# 11.net
KiCad netlist of a schematic drawn in Altium Designer
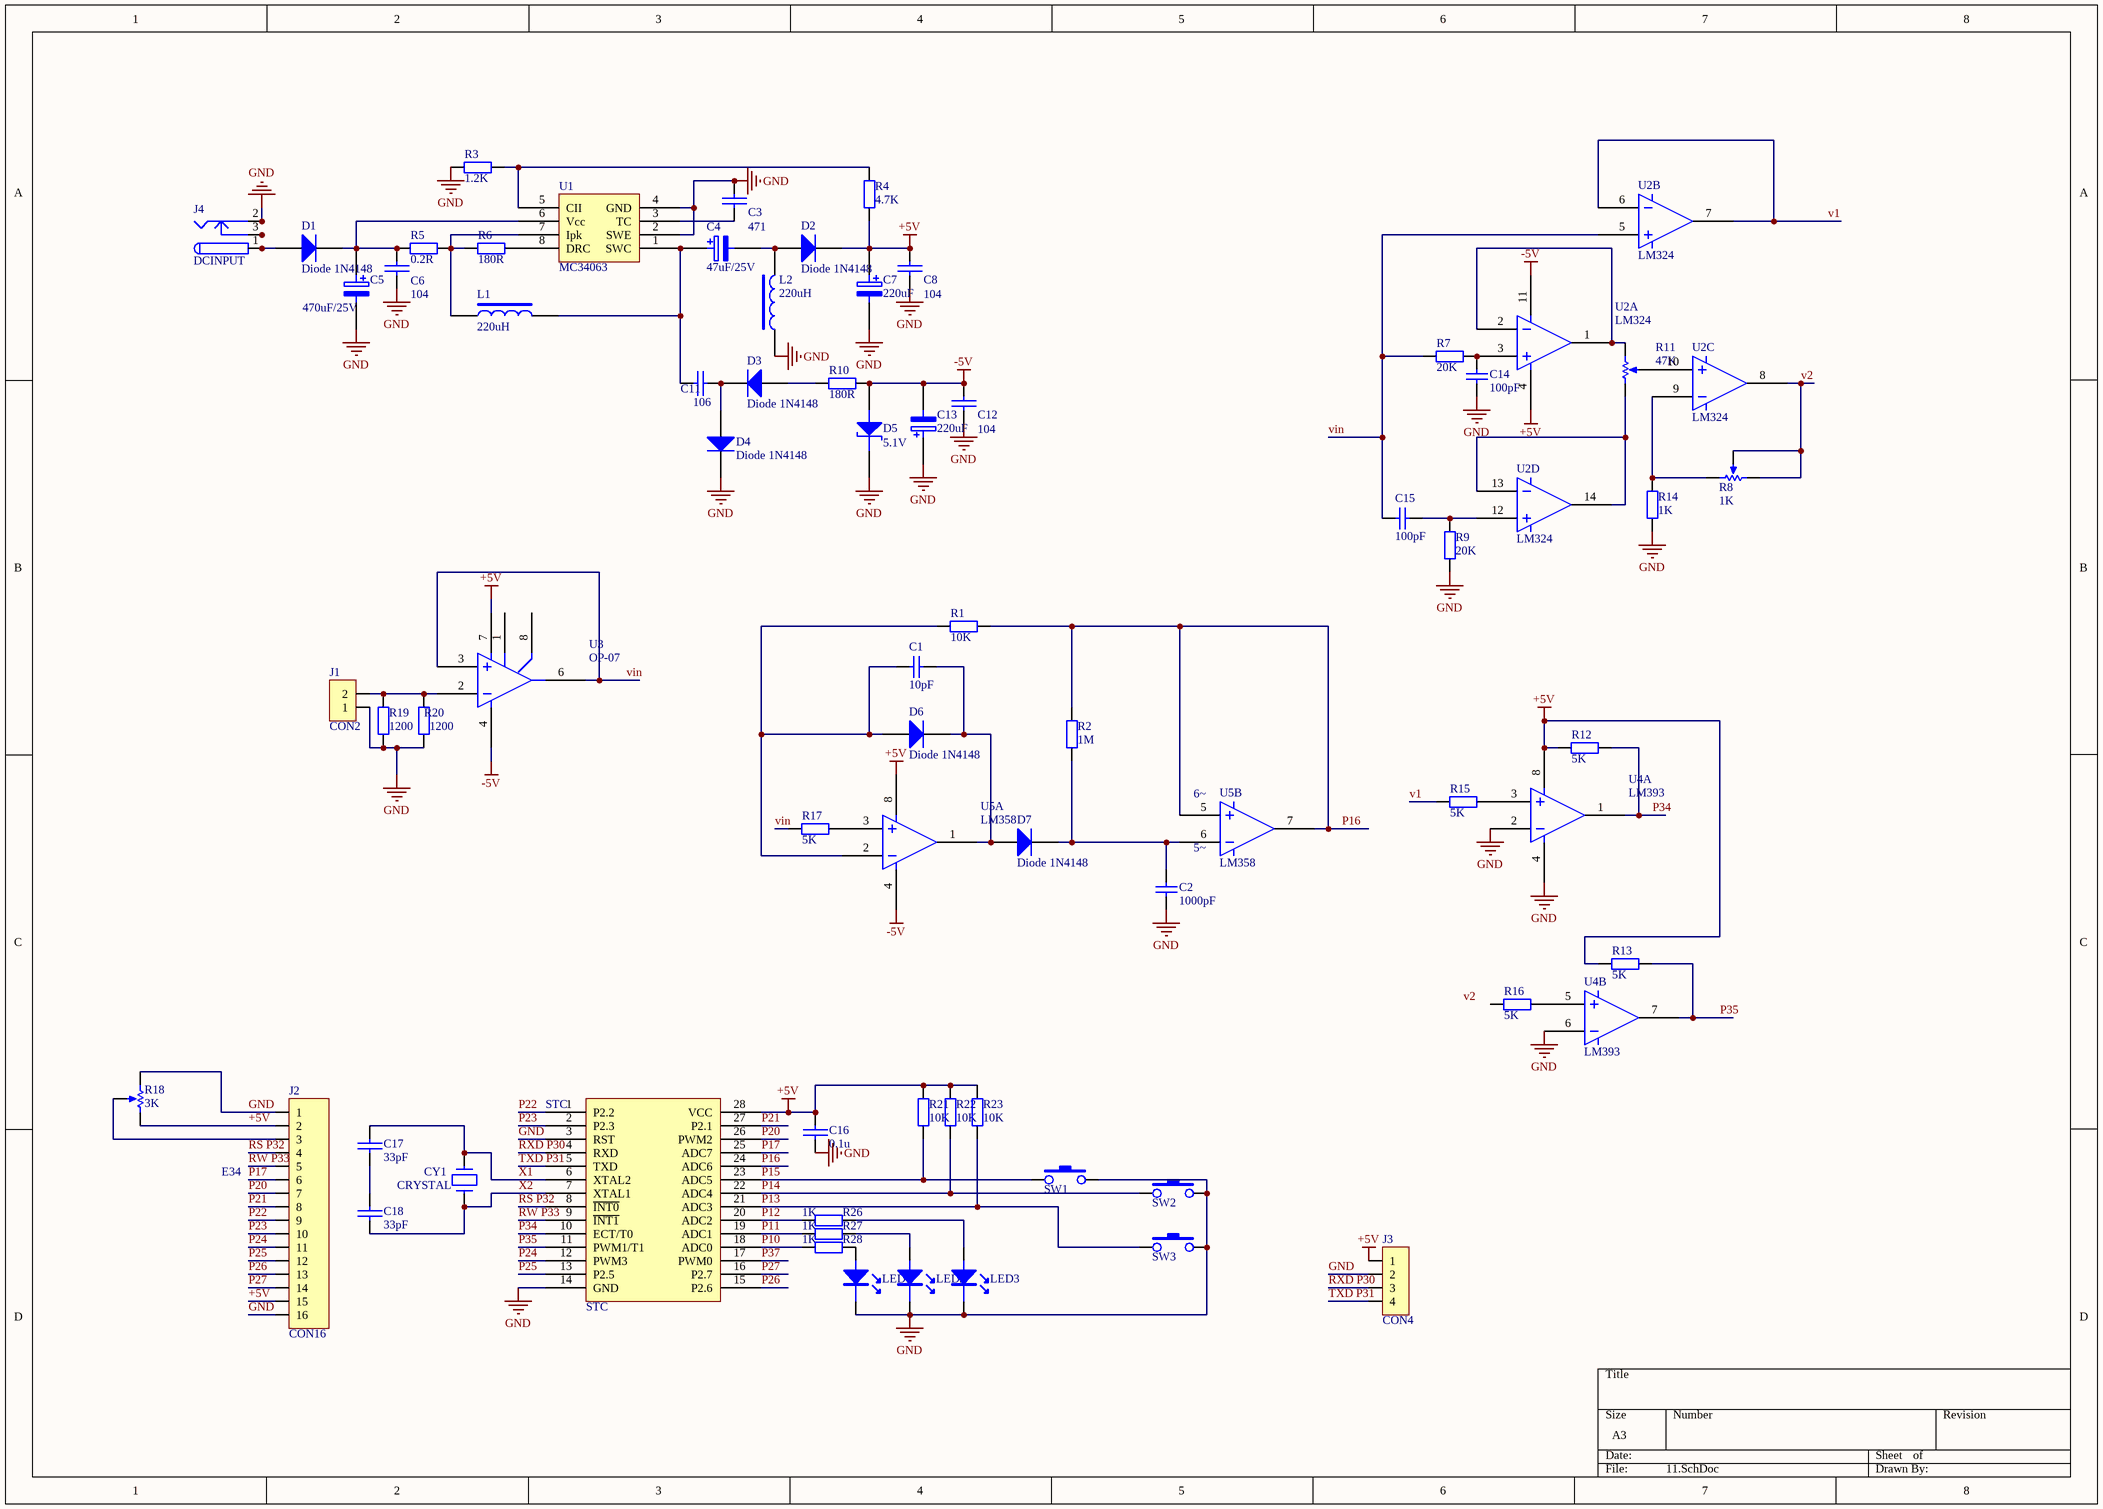
[diagram p0: 11.SchDoc]

(export (version "E")
  (design (tool "Eeschema 10.0.6"))
  (components
    (comp (ref "C1")
      (value "10pF")
      (footprint "RAD-0.2")
      (description "Capacitor")
      (fields (field (name "Comment") "Cap") (field (name "PUBLISHER") "Altium Limited"))
      (libsource (lib "Miscellaneous Devices") (part "Cap"))
    )
    (comp (ref "C2")
      (value "1000pF")
      (footprint "RAD-0.2")
      (description "Capacitor")
      (fields (field (name "Comment") "Cap") (field (name "PUBLISHER") "Altium Limited"))
      (libsource (lib "Miscellaneous Devices") (part "Cap"))
    )
    (comp (ref "C3")
      (value "471")
      (footprint "RAD0.2")
      (description "Capacitor")
      (libsource (lib "Miscellaneous Devices") (part "CAP"))
    )
    (comp (ref "C4")
      (value "47uF/25V")
      (footprint "RB.2/.3")
      (description "Electrolytic Capacitor")
      (libsource (lib "Miscellaneous Devices") (part "ELECTRO2"))
    )
    (comp (ref "C5")
      (value "470uF/25V")
      (footprint "RB.2/.3")
      (description "Electrolytic Capacitor")
      (libsource (lib "Miscellaneous Devices") (part "ELECTRO2"))
    )
    (comp (ref "C6")
      (value "104")
      (footprint "RAD0.2")
      (description "Capacitor")
      (libsource (lib "Miscellaneous Devices") (part "CAP"))
    )
    (comp (ref "C7")
      (value "220uF")
      (footprint "RB.2/.3")
      (description "Electrolytic Capacitor")
      (libsource (lib "Miscellaneous Devices") (part "ELECTRO2"))
    )
    (comp (ref "C8")
      (value "104")
      (footprint "RAD0.2")
      (description "Capacitor")
      (libsource (lib "Miscellaneous Devices") (part "CAP"))
    )
    (comp (ref "C11")
      (value "106")
      (footprint "RAD0.2")
      (description "Capacitor")
      (libsource (lib "Miscellaneous Devices") (part "CAP"))
    )
    (comp (ref "C12")
      (value "104")
      (footprint "RAD0.2")
      (description "Capacitor")
      (libsource (lib "Miscellaneous Devices") (part "CAP"))
    )
    (comp (ref "C13")
      (value "220uF")
      (footprint "RB.2/.3")
      (description "Electrolytic Capacitor")
      (libsource (lib "Miscellaneous Devices") (part "ELECTRO2"))
    )
    (comp (ref "C14")
      (value "100pF")
      (footprint "RAD-0.2")
      (description "Capacitor")
      (fields (field (name "Comment") "Cap") (field (name "PUBLISHER") "Altium Limited"))
      (libsource (lib "Miscellaneous Devices") (part "Cap"))
    )
    (comp (ref "C15")
      (value "100pF")
      (footprint "RAD-0.2")
      (description "Capacitor")
      (fields (field (name "Comment") "Cap") (field (name "PUBLISHER") "Altium Limited"))
      (libsource (lib "Miscellaneous Devices") (part "Cap"))
    )
    (comp (ref "C16") (value "0.1u") (footprint "RAD0.2") (libsource (lib "_JINXD-DEVICE") (part "CAP")))
    (comp (ref "C17") (value "33pF") (footprint "RAD0.2") (libsource (lib "_JINXD-DEVICE") (part "CAP")))
    (comp (ref "C18") (value "33pF") (footprint "RAD0.2") (libsource (lib "_JINXD-DEVICE") (part "CAP")))
    (comp (ref "CY1") (value "CRYSTAL") (footprint "CY2") (libsource (lib "_JINXD-DEVICE") (part "CRYSTAL")))
    (comp (ref "D1")
      (value "Diode 1N4148")
      (footprint "DIODE-0.4")
      (description "High Conductance Fast Diode")
      (fields (field (name "PUBLISHER") "Altium Limited"))
      (libsource (lib "Miscellaneous Devices") (part "Diode 1N4148"))
    )
    (comp (ref "D2")
      (value "Diode 1N4148")
      (footprint "DIODE-0.4")
      (description "High Conductance Fast Diode")
      (fields (field (name "PUBLISHER") "Altium Limited"))
      (libsource (lib "Miscellaneous Devices") (part "Diode 1N4148"))
    )
    (comp (ref "D3")
      (value "Diode 1N4148")
      (footprint "DIODE-0.4")
      (description "High Conductance Fast Diode")
      (fields (field (name "PUBLISHER") "Altium Limited"))
      (libsource (lib "Miscellaneous Devices") (part "Diode 1N4148"))
    )
    (comp (ref "D4")
      (value "Diode 1N4148")
      (footprint "DIODE-0.4")
      (description "High Conductance Fast Diode")
      (fields (field (name "PUBLISHER") "Altium Limited"))
      (libsource (lib "Miscellaneous Devices") (part "Diode 1N4148"))
    )
    (comp (ref "D5")
      (value "5.1V")
      (footprint "AXIAL0.4")
      (description "Zener Diode")
      (libsource (lib "Miscellaneous Devices") (part "ZENER2"))
    )
    (comp (ref "D6")
      (value "Diode 1N4148")
      (footprint "DIODE-0.4")
      (description "High Conductance Fast Diode")
      (fields (field (name "PUBLISHER") "Altium Limited"))
      (libsource (lib "Miscellaneous Devices") (part "Diode 1N4148"))
    )
    (comp (ref "D7")
      (value "Diode 1N4148")
      (footprint "DIODE-0.4")
      (description "High Conductance Fast Diode")
      (fields (field (name "PUBLISHER") "Altium Limited"))
      (libsource (lib "Miscellaneous Devices") (part "Diode 1N4148"))
    )
    (comp (ref "J1") (value "CON2") (footprint "SIP2") (libsource (lib "_JINXD-DEVICE") (part "CON2")))
    (comp (ref "J2") (value "CON16") (footprint "SIP16") (libsource (lib "_JINXD-DEVICE") (part "CON16")))
    (comp (ref "J3") (value "CON4") (footprint "SIP4") (libsource (lib "_JINXD-DEVICE") (part "CON4")))
    (comp (ref "J4")
      (value "DCINPUT")
      (footprint "DC-INPUT")
      (description "Low Voltage Power Supply Connector")
      (fields (field (name "PUBLISHER") "Altium Limited"))
      (libsource (lib "Miscellaneous Connectors") (part "PWR2.5"))
    )
    (comp (ref "L1")
      (value "220uH")
      (footprint "_Jinxd-PCB:RB.2/.4")
      (libsource (lib "Miscellaneous Devices") (part "INDUCTOR2"))
    )
    (comp (ref "L2")
      (value "220uH")
      (footprint "_Jinxd-PCB:RB.2/.4")
      (libsource (lib "") (part "INDUCTOR2_1"))
    )
    (comp (ref "LED1") (value "LED") (footprint "LED") (libsource (lib "_JINXD-DEVICE") (part "LED")))
    (comp (ref "LED2") (value "LED") (footprint "LED") (libsource (lib "_JINXD-DEVICE") (part "LED")))
    (comp (ref "LED3") (value "LED") (footprint "LED") (libsource (lib "_JINXD-DEVICE") (part "LED")))
    (comp (ref "R1")
      (value "10K")
      (footprint "AXIAL-0.4")
      (description "Resistor")
      (fields (field (name "Comment") "Res2") (field (name "PUBLISHER") "Altium Limited"))
      (libsource (lib "") (part "Res2_2"))
    )
    (comp (ref "R2")
      (value "1M")
      (footprint "AXIAL-0.4")
      (description "Resistor")
      (fields (field (name "Comment") "Res2") (field (name "PUBLISHER") "Altium Limited"))
      (libsource (lib "Miscellaneous Devices") (part "Res2"))
    )
    (comp (ref "R3")
      (value "1.2K")
      (footprint "AXIAL-0.4")
      (description "Resistor")
      (fields (field (name "PUBLISHER") "Altium Limited"))
      (libsource (lib "") (part "Res2_2"))
    )
    (comp (ref "R4")
      (value "4.7K")
      (footprint "AXIAL-0.4")
      (description "Resistor")
      (fields (field (name "PUBLISHER") "Altium Limited"))
      (libsource (lib "Miscellaneous Devices") (part "Res2"))
    )
    (comp (ref "R5")
      (value "0.2R")
      (footprint "AXIAL-0.4")
      (description "Resistor")
      (fields (field (name "PUBLISHER") "Altium Limited"))
      (libsource (lib "") (part "Res2_2"))
    )
    (comp (ref "R6")
      (value "180R")
      (footprint "AXIAL-0.4")
      (description "Resistor")
      (fields (field (name "PUBLISHER") "Altium Limited"))
      (libsource (lib "") (part "Res2_2"))
    )
    (comp (ref "R7")
      (value "20K")
      (footprint "AXIAL-0.4")
      (description "Resistor")
      (fields (field (name "PUBLISHER") "Altium Limited"))
      (libsource (lib "") (part "Res2_1"))
    )
    (comp (ref "R8")
      (value "1K")
      (footprint "VR5")
      (description "Potentiometer")
      (fields (field (name "Comment") "RPot") (field (name "PUBLISHER") "Altium Limited"))
      (libsource (lib "Miscellaneous Devices") (part "RPot"))
    )
    (comp (ref "R9")
      (value "20K")
      (footprint "AXIAL-0.4")
      (description "Resistor")
      (fields (field (name "PUBLISHER") "Altium Limited"))
      (libsource (lib "Miscellaneous Devices") (part "Res2"))
    )
    (comp (ref "R10")
      (value "180R")
      (footprint "AXIAL-0.4")
      (description "Resistor")
      (fields (field (name "PUBLISHER") "Altium Limited"))
      (libsource (lib "") (part "Res2_1"))
    )
    (comp (ref "R11")
      (value "47K")
      (footprint "VR5")
      (description "Potentiometer")
      (fields (field (name "PUBLISHER") "Altium Limited"))
      (libsource (lib "Miscellaneous Devices") (part "RPot"))
    )
    (comp (ref "R12")
      (value "5K")
      (footprint "AXIAL-0.4")
      (description "Resistor")
      (fields (field (name "Comment") "Res2") (field (name "PUBLISHER") "Altium Limited"))
      (libsource (lib "") (part "Res2_2"))
    )
    (comp (ref "R13")
      (value "5K")
      (footprint "AXIAL-0.4")
      (description "Resistor")
      (fields (field (name "Comment") "Res2") (field (name "PUBLISHER") "Altium Limited"))
      (libsource (lib "") (part "Res2_2"))
    )
    (comp (ref "R14")
      (value "1K")
      (footprint "AXIAL-0.4")
      (description "Resistor")
      (fields (field (name "Comment") "Res2") (field (name "PUBLISHER") "Altium Limited"))
      (libsource (lib "Miscellaneous Devices") (part "Res2"))
    )
    (comp (ref "R15")
      (value "5K")
      (footprint "AXIAL-0.4")
      (description "Resistor")
      (fields (field (name "PUBLISHER") "Altium Limited"))
      (libsource (lib "") (part "Res2_1"))
    )
    (comp (ref "R16")
      (value "5K")
      (footprint "AXIAL-0.4")
      (description "Resistor")
      (fields (field (name "PUBLISHER") "Altium Limited"))
      (libsource (lib "") (part "Res2_1"))
    )
    (comp (ref "R17")
      (value "5K")
      (footprint "AXIAL-0.4")
      (description "Resistor")
      (fields (field (name "Comment") "Res2") (field (name "PUBLISHER") "Altium Limited"))
      (libsource (lib "") (part "Res2_1"))
    )
    (comp (ref "R18")
      (value "3K")
      (footprint "VR5")
      (description "Potentiometer")
      (fields (field (name "Comment") "RPot") (field (name "PUBLISHER") "Altium Limited"))
      (libsource (lib "Miscellaneous Devices") (part "RPot"))
    )
    (comp (ref "R19")
      (value "1200")
      (footprint "AXIAL-0.4")
      (description "Resistor")
      (fields (field (name "Comment") "Res2") (field (name "PUBLISHER") "Altium Limited"))
      (libsource (lib "Miscellaneous Devices") (part "Res2"))
    )
    (comp (ref "R20")
      (value "1200")
      (footprint "AXIAL-0.4")
      (description "Resistor")
      (fields (field (name "Comment") "Res2") (field (name "PUBLISHER") "Altium Limited"))
      (libsource (lib "Miscellaneous Devices") (part "Res2"))
    )
    (comp (ref "R21")
      (value "10K")
      (footprint "AXIAL-0.4")
      (description "Resistor")
      (fields (field (name "Comment") "Res2") (field (name "PUBLISHER") "Altium Limited"))
      (libsource (lib "Miscellaneous Devices") (part "Res2"))
    )
    (comp (ref "R22")
      (value "10K")
      (footprint "AXIAL-0.4")
      (description "Resistor")
      (fields (field (name "Comment") "Res2") (field (name "PUBLISHER") "Altium Limited"))
      (libsource (lib "Miscellaneous Devices") (part "Res2"))
    )
    (comp (ref "R23")
      (value "10K")
      (footprint "AXIAL-0.4")
      (description "Resistor")
      (fields (field (name "Comment") "Res2") (field (name "PUBLISHER") "Altium Limited"))
      (libsource (lib "Miscellaneous Devices") (part "Res2"))
    )
    (comp (ref "R26")
      (value "1K")
      (footprint "AXIAL-0.4")
      (description "Resistor")
      (fields (field (name "Comment") "Res2") (field (name "PUBLISHER") "Altium Limited"))
      (libsource (lib "") (part "Res2_1"))
    )
    (comp (ref "R27")
      (value "1K")
      (footprint "AXIAL-0.4")
      (description "Resistor")
      (fields (field (name "Comment") "Res2") (field (name "PUBLISHER") "Altium Limited"))
      (libsource (lib "") (part "Res2_1"))
    )
    (comp (ref "R28")
      (value "1K")
      (footprint "AXIAL-0.4")
      (description "Resistor")
      (fields (field (name "Comment") "Res2") (field (name "PUBLISHER") "Altium Limited"))
      (libsource (lib "") (part "Res2_1"))
    )
    (comp (ref "STC") (value "STC") (footprint "DIP28") (libsource (lib "STC12C5628AD") (part "Component_1")))
    (comp (ref "SW1") (value "SW-PB") (footprint "SW-BP") (libsource (lib "_JINXD-DEVICE") (part "SW-PB")))
    (comp (ref "SW2") (value "SW-PB") (footprint "SW-BP") (libsource (lib "_JINXD-DEVICE") (part "SW-PB")))
    (comp (ref "SW3") (value "SW-PB") (footprint "SW-BP") (libsource (lib "_JINXD-DEVICE") (part "SW-PB")))
    (comp (ref "U1") (value "MC34063") (footprint "DIP8") (libsource (lib "_JINXD-DEVICE") (part "MC34063")))
    (comp (ref "U2")
      (value "LM324")
      (footprint "DIP-14")
      (libsource (lib "Schematic Operational Amplifiers") (part "LM324"))
    )
    (comp (ref "U3")
      (value "OP-07")
      (footprint "DIP-8")
      (libsource (lib "Schematic Operational Amplifiers") (part "OP-07"))
    )
    (comp (ref "U4")
      (value "LM393")
      (footprint "DIP-8")
      (libsource (lib "Schematic Comparator") (part "LM393"))
    )
    (comp (ref "U5")
      (value "LM358")
      (footprint "DIP-8")
      (libsource (lib "Schematic Operational Amplifiers") (part "LM358"))
    )
  )
  (nets
    (net (code "1") (name "+5V") (class "Default")
      (node (ref "C16") (pin "1") (pintype "passive"))
      (node (ref "C7") (pin "1") (pinfunction "1_1") (pintype "passive"))
      (node (ref "C8") (pin "1") (pinfunction "1_1") (pintype "passive"))
      (node (ref "D2") (pin "2") (pinfunction "K_2") (pintype "passive"))
      (node (ref "J2") (pin "15") (pinfunction "15_15") (pintype "passive"))
      (node (ref "J2") (pin "2") (pinfunction "2_2") (pintype "passive"))
      (node (ref "J3") (pin "1") (pinfunction "1_1") (pintype "passive"))
      (node (ref "R12") (pin "1") (pinfunction "1_1") (pintype "passive"))
      (node (ref "R13") (pin "1") (pinfunction "1_1") (pintype "passive"))
      (node (ref "R18") (pin "2") (pinfunction "BOT_2") (pintype "passive"))
      (node (ref "R21") (pin "2") (pinfunction "2_2") (pintype "passive"))
      (node (ref "R22") (pin "2") (pinfunction "2_2") (pintype "passive"))
      (node (ref "R23") (pin "2") (pinfunction "2_2") (pintype "passive"))
      (node (ref "R4") (pin "1") (pinfunction "1_1") (pintype "passive"))
      (node (ref "STC") (pin "28") (pinfunction "VCC_28") (pintype "passive"))
      (node (ref "U2") (pin "4") (pintype "passive"))
      (node (ref "U3") (pin "7") (pintype "passive"))
      (node (ref "U4") (pin "8") (pintype "passive"))
      (node (ref "U5") (pin "8") (pintype "passive"))
    )
    (net (code "2") (name "-5V") (class "Default")
      (node (ref "C12") (pin "1") (pinfunction "1_1") (pintype "passive"))
      (node (ref "C13") (pin "2") (pinfunction "2_2") (pintype "passive"))
      (node (ref "D5") (pin "1") (pinfunction "A_1") (pintype "passive"))
      (node (ref "R10") (pin "1") (pinfunction "1_1") (pintype "passive"))
      (node (ref "U2") (pin "11") (pintype "passive"))
      (node (ref "U3") (pin "4") (pintype "passive"))
      (node (ref "U5") (pin "4") (pintype "passive"))
    )
    (net (code "3") (name "/P10") (class "Default")
      (node (ref "R28") (pin "2") (pinfunction "2_2") (pintype "passive"))
      (node (ref "STC") (pin "18") (pinfunction "ADC0_18") (pintype "passive"))
    )
    (net (code "4") (name "/P11") (class "Default")
      (node (ref "R27") (pin "2") (pinfunction "2_2") (pintype "passive"))
      (node (ref "STC") (pin "19") (pinfunction "ADC1_19") (pintype "passive"))
    )
    (net (code "5") (name "/P12") (class "Default")
      (node (ref "R26") (pin "2") (pinfunction "2_2") (pintype "passive"))
      (node (ref "STC") (pin "20") (pinfunction "ADC2_20") (pintype "passive"))
    )
    (net (code "6") (name "/P13") (class "Default")
      (node (ref "R23") (pin "1") (pinfunction "1_1") (pintype "passive"))
      (node (ref "STC") (pin "21") (pinfunction "ADC3_21") (pintype "passive"))
      (node (ref "SW3") (pin "1") (pintype "passive"))
    )
    (net (code "7") (name "/P14") (class "Default")
      (node (ref "R22") (pin "1") (pinfunction "1_1") (pintype "passive"))
      (node (ref "STC") (pin "22") (pinfunction "ADC4_22") (pintype "passive"))
      (node (ref "SW2") (pin "1") (pintype "passive"))
    )
    (net (code "8") (name "/P15") (class "Default")
      (node (ref "R21") (pin "1") (pinfunction "1_1") (pintype "passive"))
      (node (ref "STC") (pin "23") (pinfunction "ADC5_23") (pintype "passive"))
      (node (ref "SW1") (pin "1") (pintype "passive"))
    )
    (net (code "9") (name "/P16") (class "Default")
      (node (ref "R1") (pin "2") (pinfunction "2_2") (pintype "passive"))
      (node (ref "R2") (pin "2") (pinfunction "2_2") (pintype "passive"))
      (node (ref "STC") (pin "24") (pinfunction "ADC6_24") (pintype "passive"))
      (node (ref "U5") (pin "5") (pintype "passive"))
      (node (ref "U5") (pin "7") (pintype "passive"))
    )
    (net (code "10") (name "/P17") (class "Default")
      (node (ref "J2") (pin "6") (pinfunction "6_6") (pintype "passive"))
      (node (ref "STC") (pin "25") (pinfunction "ADC7_25") (pintype "passive"))
    )
    (net (code "11") (name "/P20") (class "Default")
      (node (ref "J2") (pin "7") (pinfunction "7_7") (pintype "passive"))
      (node (ref "STC") (pin "26") (pinfunction "PWM2_26") (pintype "passive"))
    )
    (net (code "12") (name "/P21") (class "Default")
      (node (ref "J2") (pin "8") (pinfunction "8_8") (pintype "passive"))
      (node (ref "STC") (pin "27") (pinfunction "P2.1_27") (pintype "passive"))
    )
    (net (code "13") (name "/P22") (class "Default")
      (node (ref "J2") (pin "9") (pinfunction "9_9") (pintype "passive"))
      (node (ref "STC") (pin "1") (pinfunction "P2.2_1") (pintype "passive"))
    )
    (net (code "14") (name "/P23") (class "Default")
      (node (ref "J2") (pin "10") (pinfunction "10_10") (pintype "passive"))
      (node (ref "STC") (pin "2") (pinfunction "P2.3_2") (pintype "passive"))
    )
    (net (code "15") (name "/P24") (class "Default")
      (node (ref "J2") (pin "11") (pinfunction "11_11") (pintype "passive"))
      (node (ref "STC") (pin "12") (pinfunction "PWM3_12") (pintype "passive"))
    )
    (net (code "16") (name "/P25") (class "Default")
      (node (ref "J2") (pin "12") (pinfunction "12_12") (pintype "passive"))
      (node (ref "STC") (pin "13") (pinfunction "P2.5_13") (pintype "passive"))
    )
    (net (code "17") (name "/P26") (class "Default")
      (node (ref "J2") (pin "13") (pinfunction "13_13") (pintype "passive"))
      (node (ref "STC") (pin "15") (pinfunction "P2.6_15") (pintype "passive"))
    )
    (net (code "18") (name "/P27") (class "Default")
      (node (ref "J2") (pin "14") (pinfunction "14_14") (pintype "passive"))
      (node (ref "STC") (pin "16") (pinfunction "P2.7_16") (pintype "passive"))
    )
    (net (code "19") (name "/P34") (class "Default")
      (node (ref "R12") (pin "2") (pinfunction "2_2") (pintype "passive"))
      (node (ref "STC") (pin "10") (pinfunction "ECT/T0_10") (pintype "passive"))
      (node (ref "U4") (pin "1") (pintype "passive"))
    )
    (net (code "20") (name "/P35") (class "Default")
      (node (ref "R13") (pin "2") (pinfunction "2_2") (pintype "passive"))
      (node (ref "STC") (pin "11") (pinfunction "PWM1/T1_11") (pintype "passive"))
      (node (ref "U4") (pin "7") (pintype "passive"))
    )
    (net (code "21") (name "/P37") (class "Default")
      (node (ref "STC") (pin "17") (pinfunction "PWM0_17") (pintype "passive"))
    )
    (net (code "22") (name "/RS P32") (class "Default")
      (node (ref "J2") (pin "4") (pinfunction "4_4") (pintype "passive"))
      (node (ref "STC") (pin "8") (pinfunction "~{INT0}_8") (pintype "passive"))
    )
    (net (code "23") (name "/RW P33") (class "Default")
      (node (ref "J2") (pin "5") (pinfunction "5_5") (pintype "passive"))
      (node (ref "STC") (pin "9") (pinfunction "~{INT1}_9") (pintype "passive"))
    )
    (net (code "24") (name "/RXD P30") (class "Default")
      (node (ref "J3") (pin "3") (pinfunction "3_3") (pintype "passive"))
      (node (ref "STC") (pin "4") (pinfunction "RXD_4") (pintype "passive"))
    )
    (net (code "25") (name "/TXD P31") (class "Default")
      (node (ref "J3") (pin "4") (pinfunction "4_4") (pintype "passive"))
      (node (ref "STC") (pin "5") (pinfunction "TXD_5") (pintype "passive"))
    )
    (net (code "26") (name "/X1") (class "Default")
      (node (ref "C17") (pin "1") (pintype "passive"))
      (node (ref "CY1") (pin "2") (pintype "passive"))
      (node (ref "STC") (pin "6") (pinfunction "XTAL2_6") (pintype "passive"))
    )
    (net (code "27") (name "/X2") (class "Default")
      (node (ref "C18") (pin "2") (pintype "passive"))
      (node (ref "CY1") (pin "1") (pintype "passive"))
      (node (ref "STC") (pin "7") (pinfunction "XTAL1_7") (pintype "passive"))
    )
    (net (code "28") (name "/v1") (class "Default")
      (node (ref "R15") (pin "2") (pinfunction "2_2") (pintype "passive"))
      (node (ref "U2") (pin "6") (pintype "passive"))
      (node (ref "U2") (pin "7") (pintype "passive"))
    )
    (net (code "29") (name "/v2") (class "Default")
      (node (ref "R8") (pin "1") (pinfunction "TOP_1") (pintype "passive"))
      (node (ref "R8") (pin "3") (pinfunction "TAP_3") (pintype "passive"))
      (node (ref "U2") (pin "8") (pintype "passive"))
    )
    (net (code "30") (name "/vin") (class "Default")
      (node (ref "C15") (pin "1") (pinfunction "1_1") (pintype "passive"))
      (node (ref "R17") (pin "2") (pinfunction "2_2") (pintype "passive"))
      (node (ref "R7") (pin "2") (pinfunction "2_2") (pintype "passive"))
      (node (ref "U2") (pin "5") (pintype "passive"))
      (node (ref "U3") (pin "3") (pintype "passive"))
      (node (ref "U3") (pin "6") (pintype "passive"))
    )
    (net (code "31") (name "GND") (class "Default")
      (node (ref "C12") (pin "2") (pinfunction "2_2") (pintype "passive"))
      (node (ref "C13") (pin "1") (pinfunction "1_1") (pintype "passive"))
      (node (ref "C14") (pin "1") (pinfunction "1_1") (pintype "passive"))
      (node (ref "C16") (pin "2") (pintype "passive"))
      (node (ref "C2") (pin "1") (pinfunction "1_1") (pintype "passive"))
      (node (ref "C3") (pin "1") (pinfunction "1_1") (pintype "passive"))
      (node (ref "C5") (pin "2") (pinfunction "2_2") (pintype "passive"))
      (node (ref "C6") (pin "2") (pinfunction "2_2") (pintype "passive"))
      (node (ref "C7") (pin "2") (pinfunction "2_2") (pintype "passive"))
      (node (ref "C8") (pin "2") (pinfunction "2_2") (pintype "passive"))
      (node (ref "D4") (pin "2") (pinfunction "K_2") (pintype "passive"))
      (node (ref "D5") (pin "2") (pinfunction "K_2") (pintype "passive"))
      (node (ref "J1") (pin "1") (pinfunction "1_1") (pintype "passive"))
      (node (ref "J2") (pin "1") (pinfunction "1_1") (pintype "passive"))
      (node (ref "J2") (pin "16") (pinfunction "16_16") (pintype "passive"))
      (node (ref "J3") (pin "2") (pinfunction "2_2") (pintype "passive"))
      (node (ref "J4") (pin "2") (pinfunction "2_2") (pintype "power_in"))
      (node (ref "J4") (pin "2A") (pinfunction "2A_2A") (pintype "power_in"))
      (node (ref "J4") (pin "2B") (pinfunction "2B_2B") (pintype "power_in"))
      (node (ref "L2") (pin "1") (pinfunction "1_1") (pintype "passive"))
      (node (ref "LED1") (pin "K") (pintype "passive"))
      (node (ref "LED2") (pin "K") (pintype "passive"))
      (node (ref "LED3") (pin "K") (pintype "passive"))
      (node (ref "R14") (pin "1") (pinfunction "1_1") (pintype "passive"))
      (node (ref "R18") (pin "1") (pinfunction "TOP_1") (pintype "passive"))
      (node (ref "R19") (pin "1") (pinfunction "1_1") (pintype "passive"))
      (node (ref "R20") (pin "1") (pinfunction "1_1") (pintype "passive"))
      (node (ref "R3") (pin "1") (pinfunction "1_1") (pintype "passive"))
      (node (ref "R9") (pin "1") (pinfunction "1_1") (pintype "passive"))
      (node (ref "STC") (pin "14") (pinfunction "GND_14") (pintype "passive"))
      (node (ref "STC") (pin "3") (pinfunction "RST_3") (pintype "passive"))
      (node (ref "SW1") (pin "2") (pintype "passive"))
      (node (ref "SW2") (pin "2") (pintype "passive"))
      (node (ref "SW3") (pin "2") (pintype "passive"))
      (node (ref "U1") (pin "2") (pinfunction "SWE_2") (pintype "passive"))
      (node (ref "U1") (pin "4") (pinfunction "GND_4") (pintype "passive"))
      (node (ref "U4") (pin "2") (pintype "passive"))
      (node (ref "U4") (pin "4") (pintype "passive"))
      (node (ref "U4") (pin "6") (pintype "passive"))
    )
    (net (code "32") (name "Net-(C14-Pad2)") (class "Default")
      (node (ref "C14") (pin "2") (pinfunction "2_2") (pintype "passive"))
      (node (ref "R7") (pin "1") (pinfunction "1_1") (pintype "passive"))
      (node (ref "U2") (pin "3") (pintype "passive"))
    )
    (net (code "33") (name "Net-(C15-Pad2)") (class "Default")
      (node (ref "C15") (pin "2") (pinfunction "2_2") (pintype "passive"))
      (node (ref "R9") (pin "2") (pinfunction "2_2") (pintype "passive"))
      (node (ref "U2") (pin "12") (pintype "passive"))
    )
    (net (code "34") (name "Net-(C17-Pad2)") (class "Default")
      (node (ref "C17") (pin "2") (pintype "passive"))
      (node (ref "C18") (pin "1") (pintype "passive"))
    )
    (net (code "35") (name "Net-(D1-A)") (class "Default")
      (node (ref "D1") (pin "1") (pinfunction "A_1") (pintype "passive"))
      (node (ref "J4") (pin "1") (pinfunction "1_1") (pintype "power_in"))
      (node (ref "J4") (pin "1A") (pinfunction "1A_1A") (pintype "power_in"))
      (node (ref "J4") (pin "1B") (pinfunction "1B_1B") (pintype "power_in"))
    )
    (net (code "36") (name "Net-(D1-K)") (class "Default")
      (node (ref "C5") (pin "1") (pinfunction "1_1") (pintype "passive"))
      (node (ref "C6") (pin "1") (pinfunction "1_1") (pintype "passive"))
      (node (ref "D1") (pin "2") (pinfunction "K_2") (pintype "passive"))
      (node (ref "R5") (pin "1") (pinfunction "1_1") (pintype "passive"))
      (node (ref "U1") (pin "6") (pinfunction "Vcc_6") (pintype "passive"))
    )
    (net (code "37") (name "Net-(D2-A)") (class "Default")
      (node (ref "C4") (pin "2") (pinfunction "2_2") (pintype "passive"))
      (node (ref "D2") (pin "1") (pinfunction "A_1") (pintype "passive"))
      (node (ref "L2") (pin "2") (pinfunction "2_2") (pintype "passive"))
    )
    (net (code "38") (name "Net-(D3-A)") (class "Default")
      (node (ref "D3") (pin "1") (pinfunction "A_1") (pintype "passive"))
      (node (ref "R10") (pin "2") (pinfunction "2_2") (pintype "passive"))
    )
    (net (code "39") (name "Net-(D3-K)") (class "Default")
      (node (ref "C11") (pin "2") (pinfunction "2_2") (pintype "passive"))
      (node (ref "D3") (pin "2") (pinfunction "K_2") (pintype "passive"))
      (node (ref "D4") (pin "1") (pinfunction "A_1") (pintype "passive"))
    )
    (net (code "40") (name "Net-(D6-A)") (class "Default")
      (node (ref "C1") (pin "1") (pinfunction "1_1") (pintype "passive"))
      (node (ref "D6") (pin "1") (pinfunction "A_1") (pintype "passive"))
      (node (ref "R1") (pin "1") (pinfunction "1_1") (pintype "passive"))
      (node (ref "U5") (pin "2") (pintype "passive"))
    )
    (net (code "41") (name "Net-(D6-K)") (class "Default")
      (node (ref "C1") (pin "2") (pinfunction "2_2") (pintype "passive"))
      (node (ref "D6") (pin "2") (pinfunction "K_2") (pintype "passive"))
      (node (ref "D7") (pin "1") (pinfunction "A_1") (pintype "passive"))
      (node (ref "U5") (pin "1") (pintype "passive"))
    )
    (net (code "42") (name "Net-(D7-K)") (class "Default")
      (node (ref "C2") (pin "2") (pinfunction "2_2") (pintype "passive"))
      (node (ref "D7") (pin "2") (pinfunction "K_2") (pintype "passive"))
      (node (ref "R2") (pin "1") (pinfunction "1_1") (pintype "passive"))
      (node (ref "U5") (pin "6") (pintype "passive"))
    )
    (net (code "43") (name "Net-(J1-Pad2)") (class "Default")
      (node (ref "J1") (pin "2") (pinfunction "2_2") (pintype "passive"))
      (node (ref "R19") (pin "2") (pinfunction "2_2") (pintype "passive"))
      (node (ref "R20") (pin "2") (pinfunction "2_2") (pintype "passive"))
      (node (ref "U3") (pin "2") (pintype "passive"))
    )
    (net (code "44") (name "Net-(J4-Pad3)") (class "Default")
      (node (ref "J4") (pin "3") (pinfunction "3_3") (pintype "power_in"))
      (node (ref "J4") (pin "3A") (pinfunction "3A_3A") (pintype "power_in"))
      (node (ref "J4") (pin "3B") (pinfunction "3B_3B") (pintype "power_in"))
    )
    (net (code "45") (name "Net-(LED1-PadA)") (class "Default")
      (node (ref "LED1") (pin "A") (pintype "passive"))
      (node (ref "R28") (pin "1") (pinfunction "1_1") (pintype "passive"))
    )
    (net (code "46") (name "Net-(LED2-PadA)") (class "Default")
      (node (ref "LED2") (pin "A") (pintype "passive"))
      (node (ref "R27") (pin "1") (pinfunction "1_1") (pintype "passive"))
    )
    (net (code "47") (name "Net-(LED3-PadA)") (class "Default")
      (node (ref "LED3") (pin "A") (pintype "passive"))
      (node (ref "R26") (pin "1") (pinfunction "1_1") (pintype "passive"))
    )
    (net (code "48") (name "Net-(R8-BOT)") (class "Default")
      (node (ref "R14") (pin "2") (pinfunction "2_2") (pintype "passive"))
      (node (ref "R8") (pin "2") (pinfunction "BOT_2") (pintype "passive"))
      (node (ref "U2") (pin "9") (pintype "passive"))
    )
    (net (code "49") (name "Net-(R11-BOT)") (class "Default")
      (node (ref "R11") (pin "2") (pinfunction "BOT_2") (pintype "passive"))
      (node (ref "U2") (pin "1") (pintype "passive"))
      (node (ref "U2") (pin "2") (pintype "passive"))
    )
    (net (code "50") (name "Net-(R11-TAP)") (class "Default")
      (node (ref "R11") (pin "3") (pinfunction "TAP_3") (pintype "passive"))
      (node (ref "U2") (pin "10") (pintype "passive"))
    )
    (net (code "51") (name "Net-(R11-TOP)") (class "Default")
      (node (ref "R11") (pin "1") (pinfunction "TOP_1") (pintype "passive"))
      (node (ref "U2") (pin "13") (pintype "passive"))
      (node (ref "U2") (pin "14") (pintype "passive"))
    )
    (net (code "52") (name "Net-(R15-Pad1)") (class "Default")
      (node (ref "R15") (pin "1") (pinfunction "1_1") (pintype "passive"))
      (node (ref "U4") (pin "3") (pintype "passive"))
    )
    (net (code "53") (name "Net-(R16-Pad1)") (class "Default")
      (node (ref "R16") (pin "1") (pinfunction "1_1") (pintype "passive"))
      (node (ref "U4") (pin "5") (pintype "passive"))
    )
    (net (code "54") (name "Net-(R17-Pad1)") (class "Default")
      (node (ref "R17") (pin "1") (pinfunction "1_1") (pintype "passive"))
      (node (ref "U5") (pin "3") (pintype "passive"))
    )
    (net (code "55") (name "Net-(R18-TAP)") (class "Default")
      (node (ref "J2") (pin "3") (pinfunction "3_3") (pintype "passive"))
      (node (ref "R18") (pin "3") (pinfunction "TAP_3") (pintype "passive"))
    )
    (net (code "56") (name "Net-(U1-CII)") (class "Default")
      (node (ref "R3") (pin "2") (pinfunction "2_2") (pintype "passive"))
      (node (ref "R4") (pin "2") (pinfunction "2_2") (pintype "passive"))
      (node (ref "U1") (pin "5") (pinfunction "CII_5") (pintype "passive"))
    )
    (net (code "57") (name "Net-(U1-DRC)") (class "Default")
      (node (ref "R6") (pin "2") (pinfunction "2_2") (pintype "passive"))
      (node (ref "U1") (pin "8") (pinfunction "DRC_8") (pintype "passive"))
    )
    (net (code "58") (name "Net-(U1-Ipk)") (class "Default")
      (node (ref "L1") (pin "1") (pinfunction "1_1") (pintype "passive"))
      (node (ref "R5") (pin "2") (pinfunction "2_2") (pintype "passive"))
      (node (ref "R6") (pin "1") (pinfunction "1_1") (pintype "passive"))
      (node (ref "U1") (pin "7") (pinfunction "Ipk_7") (pintype "passive"))
    )
    (net (code "59") (name "Net-(U1-SWC)") (class "Default")
      (node (ref "C11") (pin "1") (pinfunction "1_1") (pintype "passive"))
      (node (ref "C4") (pin "1") (pinfunction "1_1") (pintype "passive"))
      (node (ref "L1") (pin "2") (pinfunction "2_2") (pintype "passive"))
      (node (ref "U1") (pin "1") (pinfunction "SWC_1") (pintype "passive"))
    )
    (net (code "60") (name "Net-(U1-TC)") (class "Default")
      (node (ref "C3") (pin "2") (pinfunction "2_2") (pintype "passive"))
      (node (ref "U1") (pin "3") (pinfunction "TC_3") (pintype "passive"))
    )
    (net (code "61") (name "unconnected-(R16-Pad2)") (class "Default")
      (node (ref "R16") (pin "2") (pinfunction "2_2") (pintype "passive"))
    )
    (net (code "62") (name "unconnected-(U3-Pad1)") (class "Default")
      (node (ref "U3") (pin "1") (pintype "passive"))
    )
    (net (code "63") (name "unconnected-(U3-Pad8)") (class "Default")
      (node (ref "U3") (pin "8") (pintype "passive"))
    )
  )
)
